# Schematic.net
KiCad netlist of a schematic drawn in EasyEDA Pro
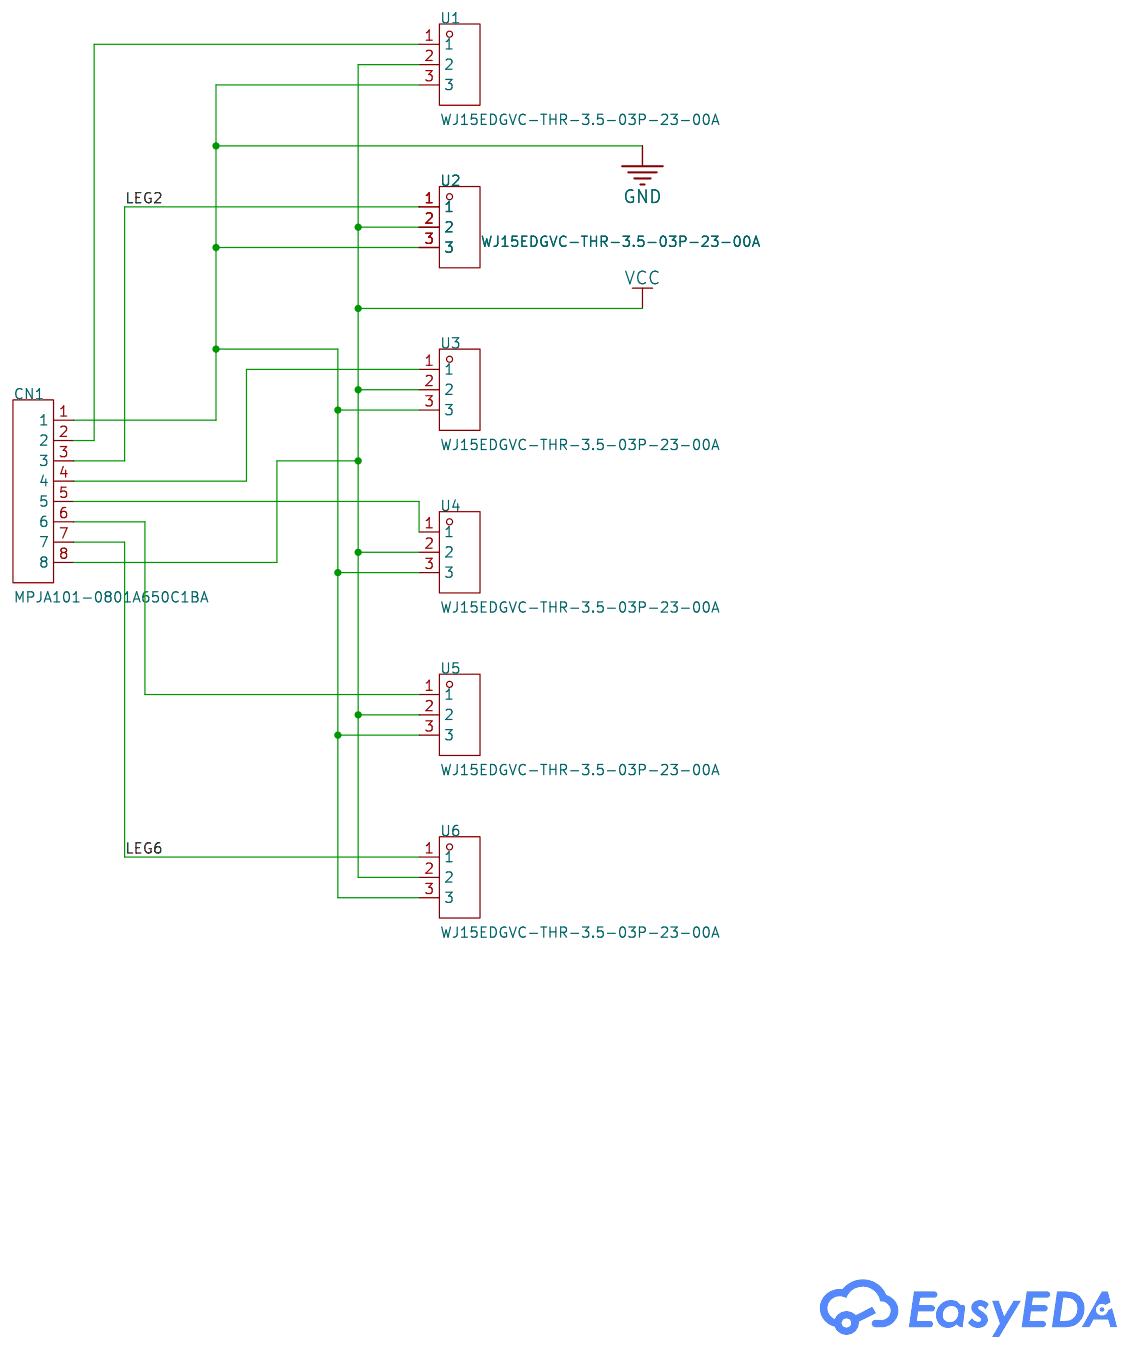
[diagram p0: schematic sheet]

(export (version "E")
  (design (tool "Eeschema 10.0.6"))
  (components
    (comp (ref "CN1")
      (value "MPJA101-0801A650C1BA")
      (footprint "easyedapro:HDR-TH_8P-P3.96-V-M_C9900009548")
      (libsource (lib "easyedapro") (part "MPJA101-0801A650C1BA"))
    )
    (comp (ref "U1")
      (value "WJ15EDGVC-THR-3.5-03P-23-00A")
      (footprint "easyedapro:CONN-TH_3P-P3.50_WJ15EDGVC-THR-3.5-03P-23-00A")
      (libsource (lib "easyedapro") (part "WJ15EDGVC-THR-3.5-03P-23-00A"))
    )
    (comp (ref "U2")
      (value "WJ15EDGVC-THR-3.5-03P-23-00A")
      (footprint "easyedapro:CONN-TH_3P-P3.50_WJ15EDGVC-THR-3.5-03P-23-00A")
      (libsource (lib "easyedapro") (part "WJ15EDGVC-THR-3.5-03P-23-00A"))
    )
    (comp (ref "U3")
      (value "WJ15EDGVC-THR-3.5-03P-23-00A")
      (footprint "easyedapro:CONN-TH_3P-P3.50_WJ15EDGVC-THR-3.5-03P-23-00A")
      (libsource (lib "easyedapro") (part "WJ15EDGVC-THR-3.5-03P-23-00A"))
    )
    (comp (ref "U4")
      (value "WJ15EDGVC-THR-3.5-03P-23-00A")
      (footprint "easyedapro:CONN-TH_3P-P3.50_WJ15EDGVC-THR-3.5-03P-23-00A")
      (libsource (lib "easyedapro") (part "WJ15EDGVC-THR-3.5-03P-23-00A"))
    )
    (comp (ref "U5")
      (value "WJ15EDGVC-THR-3.5-03P-23-00A")
      (footprint "easyedapro:CONN-TH_3P-P3.50_WJ15EDGVC-THR-3.5-03P-23-00A")
      (libsource (lib "easyedapro") (part "WJ15EDGVC-THR-3.5-03P-23-00A"))
    )
    (comp (ref "U6")
      (value "WJ15EDGVC-THR-3.5-03P-23-00A")
      (footprint "easyedapro:CONN-TH_3P-P3.50_WJ15EDGVC-THR-3.5-03P-23-00A")
      (libsource (lib "easyedapro") (part "WJ15EDGVC-THR-3.5-03P-23-00A"))
    )
  )
  (nets
    (net (code "1") (name "/LEG2") (class "Default")
      (node (ref "CN1") (pin "3") (pinfunction "3_3") (pintype "unspecified"))
      (node (ref "U2") (pin "1") (pinfunction "1_1") (pintype "unspecified"))
    )
    (net (code "2") (name "/LEG6") (class "Default")
      (node (ref "CN1") (pin "7") (pinfunction "7_7") (pintype "unspecified"))
      (node (ref "U6") (pin "1") (pinfunction "1_1") (pintype "unspecified"))
    )
    (net (code "3") (name "GND") (class "Default")
      (node (ref "CN1") (pin "1") (pinfunction "1_1") (pintype "unspecified"))
      (node (ref "U1") (pin "3") (pinfunction "3_3") (pintype "unspecified"))
      (node (ref "U2") (pin "3") (pinfunction "3_3") (pintype "unspecified"))
      (node (ref "U3") (pin "3") (pinfunction "3_3") (pintype "unspecified"))
      (node (ref "U4") (pin "3") (pinfunction "3_3") (pintype "unspecified"))
      (node (ref "U5") (pin "3") (pinfunction "3_3") (pintype "unspecified"))
      (node (ref "U6") (pin "3") (pinfunction "3_3") (pintype "unspecified"))
    )
    (net (code "4") (name "Net-(CN1-Pad2)") (class "Default")
      (node (ref "CN1") (pin "2") (pinfunction "2_2") (pintype "unspecified"))
      (node (ref "U1") (pin "1") (pinfunction "1_1") (pintype "unspecified"))
    )
    (net (code "5") (name "Net-(CN1-Pad4)") (class "Default")
      (node (ref "CN1") (pin "4") (pinfunction "4_4") (pintype "unspecified"))
      (node (ref "U3") (pin "1") (pinfunction "1_1") (pintype "unspecified"))
    )
    (net (code "6") (name "Net-(CN1-Pad5)") (class "Default")
      (node (ref "CN1") (pin "5") (pinfunction "5_5") (pintype "unspecified"))
      (node (ref "U4") (pin "1") (pinfunction "1_1") (pintype "unspecified"))
    )
    (net (code "7") (name "Net-(CN1-Pad6)") (class "Default")
      (node (ref "CN1") (pin "6") (pinfunction "6_6") (pintype "unspecified"))
      (node (ref "U5") (pin "1") (pinfunction "1_1") (pintype "unspecified"))
    )
    (net (code "8") (name "VCC") (class "Default")
      (node (ref "CN1") (pin "8") (pinfunction "8_8") (pintype "unspecified"))
      (node (ref "U1") (pin "2") (pinfunction "2_2") (pintype "unspecified"))
      (node (ref "U2") (pin "2") (pinfunction "2_2") (pintype "unspecified"))
      (node (ref "U3") (pin "2") (pinfunction "2_2") (pintype "unspecified"))
      (node (ref "U4") (pin "2") (pinfunction "2_2") (pintype "unspecified"))
      (node (ref "U5") (pin "2") (pinfunction "2_2") (pintype "unspecified"))
      (node (ref "U6") (pin "2") (pinfunction "2_2") (pintype "unspecified"))
    )
  )
)
